# bldc-interface.net
KiCad netlist of a schematic drawn in EAGLE
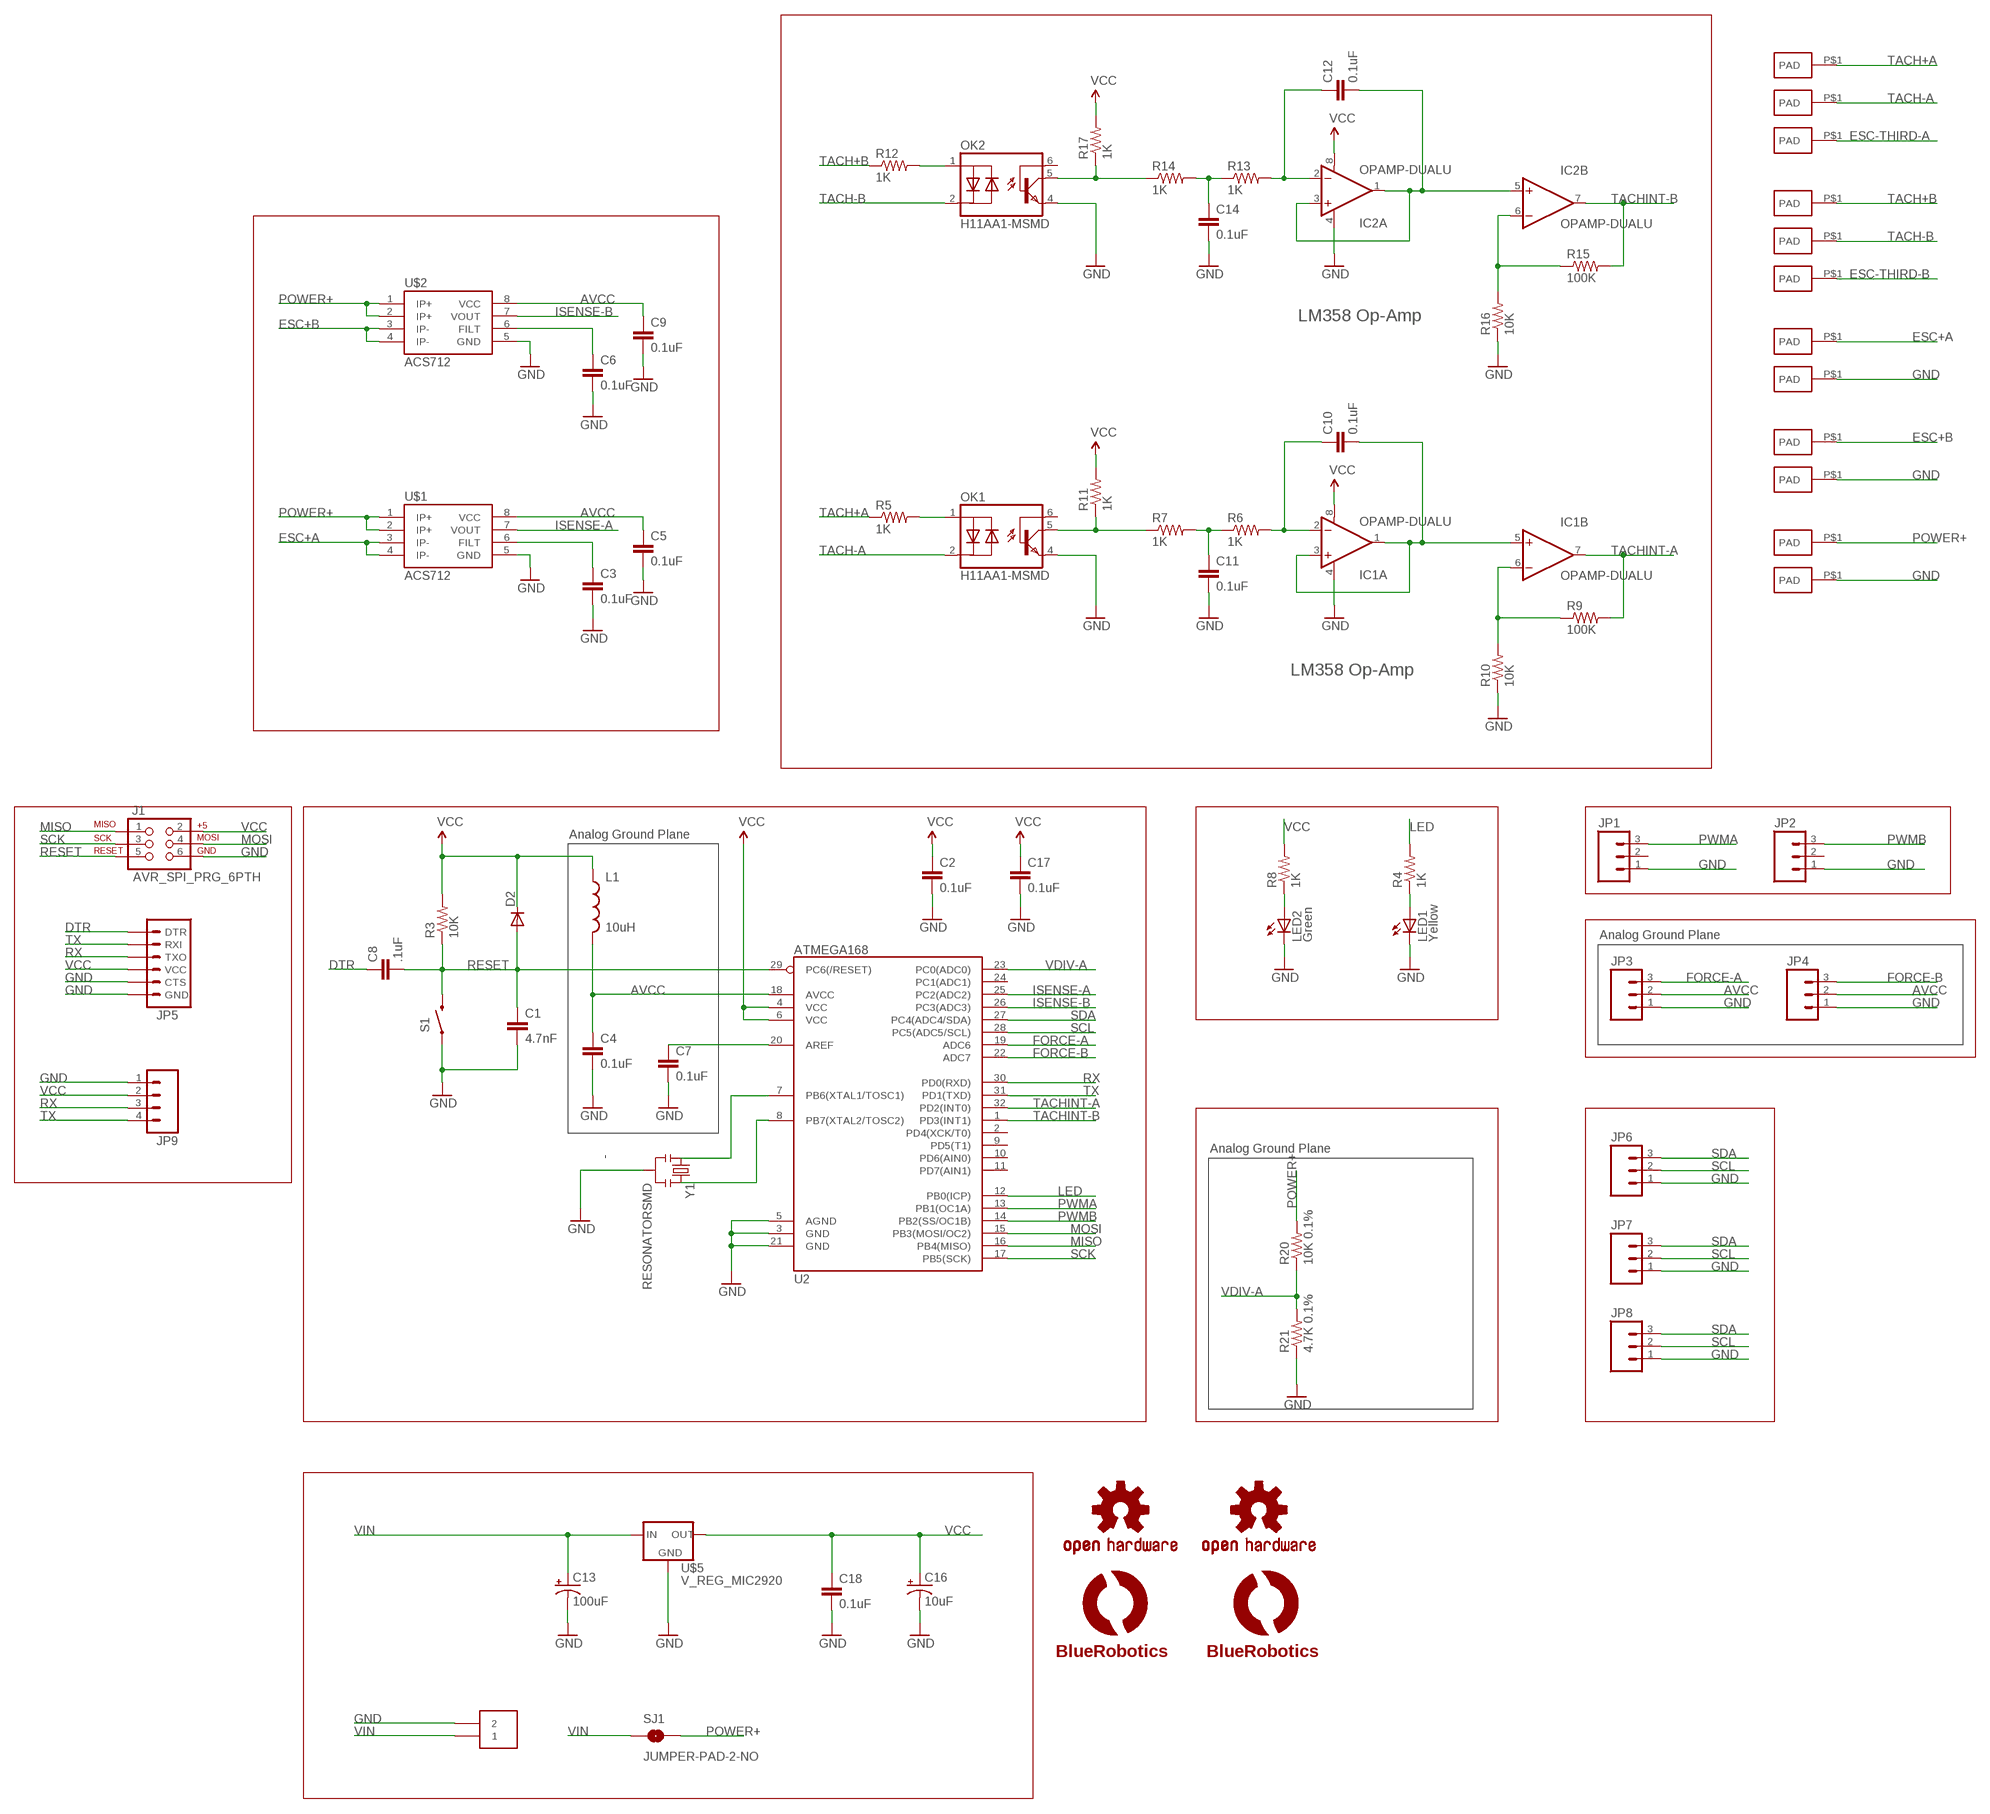
[diagram p0: schematic, sheet 1]

(export (version "E")
  (design (tool "Eeschema 10.0.6"))
  (components
    (comp (ref "C1")
      (value "4.7nF")
      (footprint "eagle-import:0603-CAP")
      (libsource (lib "eagle-import") (part "CAP0603-CAP"))
    )
    (comp (ref "C2")
      (value "0.1uF")
      (footprint "eagle-import:0603-CAP")
      (libsource (lib "eagle-import") (part "SparkFun2_CAP0603-CAP"))
    )
    (comp (ref "C3")
      (value "0.1uF")
      (footprint "eagle-import:0603-CAP")
      (libsource (lib "eagle-import") (part "SparkFun-Capacitors_CAP0603-CAP"))
    )
    (comp (ref "C4")
      (value "0.1uF")
      (footprint "eagle-import:0603-CAP")
      (libsource (lib "eagle-import") (part "CAP0603-CAP"))
    )
    (comp (ref "C5")
      (value "0.1uF")
      (footprint "eagle-import:0603-CAP")
      (libsource (lib "eagle-import") (part "SparkFun-Capacitors_CAP0603-CAP"))
    )
    (comp (ref "C6")
      (value "0.1uF")
      (footprint "eagle-import:0603-CAP")
      (libsource (lib "eagle-import") (part "SparkFun-Capacitors_CAP0603-CAP"))
    )
    (comp (ref "C7")
      (value "0.1uF")
      (footprint "eagle-import:0603-CAP")
      (libsource (lib "eagle-import") (part "CAP0603-CAP"))
    )
    (comp (ref "C8")
      (value ".1uF")
      (footprint "eagle-import:0603-CAP")
      (libsource (lib "eagle-import") (part "CAP0603-CAP"))
    )
    (comp (ref "C9")
      (value "0.1uF")
      (footprint "eagle-import:0603-CAP")
      (libsource (lib "eagle-import") (part "SparkFun-Capacitors_CAP0603-CAP"))
    )
    (comp (ref "C10")
      (value "0.1uF")
      (footprint "eagle-import:0603-CAP")
      (libsource (lib "eagle-import") (part "SparkFun-Capacitors_CAP0603-CAP"))
    )
    (comp (ref "C11")
      (value "0.1uF")
      (footprint "eagle-import:0603-CAP")
      (libsource (lib "eagle-import") (part "SparkFun-Capacitors_CAP0603-CAP"))
    )
    (comp (ref "C12")
      (value "0.1uF")
      (footprint "eagle-import:0603-CAP")
      (libsource (lib "eagle-import") (part "SparkFun-Capacitors_CAP0603-CAP"))
    )
    (comp (ref "C13")
      (value "100uF")
      (footprint "eagle-import:CPOL-RADIAL-100UF-25V")
      (libsource (lib "eagle-import") (part "CAP_POLPTH1"))
    )
    (comp (ref "C14")
      (value "0.1uF")
      (footprint "eagle-import:0603-CAP")
      (libsource (lib "eagle-import") (part "SparkFun-Capacitors_CAP0603-CAP"))
    )
    (comp (ref "C16")
      (value "10uF")
      (footprint "eagle-import:EIA3216")
      (libsource (lib "eagle-import") (part "CAP_POL1206"))
    )
    (comp (ref "C17")
      (value "0.1uF")
      (footprint "eagle-import:0603-CAP")
      (libsource (lib "eagle-import") (part "SparkFun2_CAP0603-CAP"))
    )
    (comp (ref "C18")
      (value "0.1uF")
      (footprint "eagle-import:0603-CAP")
      (libsource (lib "eagle-import") (part "CAP0603-CAP"))
    )
    (comp (ref "D2")
      (value "DIODESOD")
      (footprint "eagle-import:SOD-323")
      (libsource (lib "eagle-import") (part "DIODESOD"))
    )
    (comp (ref "IC1")
      (value "OPAMP-DUALU")
      (footprint "eagle-import:SO08")
      (libsource (lib "eagle-import") (part "OPAMP-DUALU"))
    )
    (comp (ref "IC2")
      (value "OPAMP-DUALU")
      (footprint "eagle-import:SO08")
      (libsource (lib "eagle-import") (part "OPAMP-DUALU"))
    )
    (comp (ref "J1")
      (value "AVR_SPI_PRG_6PTH")
      (footprint "eagle-import:2X3")
      (libsource (lib "eagle-import") (part "AVR_SPI_PRG_6PTH"))
    )
    (comp (ref "JP1")
      (value "M03PTH")
      (footprint "eagle-import:1X03")
      (libsource (lib "eagle-import") (part "M03PTH"))
    )
    (comp (ref "JP2")
      (value "M03PTH")
      (footprint "eagle-import:1X03")
      (libsource (lib "eagle-import") (part "M03PTH"))
    )
    (comp (ref "JP3")
      (value "M03PTH")
      (footprint "eagle-import:1X03")
      (libsource (lib "eagle-import") (part "M03PTH"))
    )
    (comp (ref "JP4")
      (value "M03PTH")
      (footprint "eagle-import:1X03")
      (libsource (lib "eagle-import") (part "M03PTH"))
    )
    (comp (ref "JP5")
      (value "ARDUINO_SERIAL_PROGRAMPTH")
      (footprint "eagle-import:1X06")
      (libsource (lib "eagle-import") (part "ARDUINO_SERIAL_PROGRAMPTH"))
    )
    (comp (ref "JP6")
      (value "M03PTH")
      (footprint "eagle-import:1X03")
      (libsource (lib "eagle-import") (part "M03PTH"))
    )
    (comp (ref "JP7")
      (value "M03PTH")
      (footprint "eagle-import:1X03")
      (libsource (lib "eagle-import") (part "M03PTH"))
    )
    (comp (ref "JP8")
      (value "M03PTH")
      (footprint "eagle-import:1X03")
      (libsource (lib "eagle-import") (part "M03PTH"))
    )
    (comp (ref "JP9")
      (value "M04PTH")
      (footprint "eagle-import:1X04")
      (libsource (lib "eagle-import") (part "M04PTH"))
    )
    (comp (ref "L1")
      (value "10uH")
      (footprint "eagle-import:0603")
      (libsource (lib "eagle-import") (part "INDUCTOR0603"))
    )
    (comp (ref "LED1")
      (value "Yellow")
      (footprint "eagle-import:LED-0603")
      (libsource (lib "eagle-import") (part "LED0603"))
    )
    (comp (ref "LED2")
      (value "Green")
      (footprint "eagle-import:LED-0603")
      (libsource (lib "eagle-import") (part "LED0603"))
    )
    (comp (ref "LOGO1")
      (value "OSHW-LOGOS")
      (footprint "eagle-import:OSHW-LOGO-S")
      (libsource (lib "eagle-import") (part "OSHW-LOGOS"))
    )
    (comp (ref "LOGO2")
      (value "OSHW-LOGOM")
      (footprint "eagle-import:OSHW-LOGO-M")
      (libsource (lib "eagle-import") (part "OSHW-LOGOM"))
    )
    (comp (ref "OK1")
      (value "H11AA1-MSMD")
      (footprint "eagle-import:DIL6-SMD")
      (libsource (lib "eagle-import") (part "H11AA1-MSMD"))
    )
    (comp (ref "OK2")
      (value "H11AA1-MSMD")
      (footprint "eagle-import:DIL6-SMD")
      (libsource (lib "eagle-import") (part "H11AA1-MSMD"))
    )
    (comp (ref "R3")
      (value "10K")
      (footprint "eagle-import:0603-RES")
      (libsource (lib "eagle-import") (part "RESISTOR0603-RES"))
    )
    (comp (ref "R4")
      (value "1K")
      (footprint "eagle-import:0603-RES")
      (libsource (lib "eagle-import") (part "RESISTOR0603-RES"))
    )
    (comp (ref "R5")
      (value "1K")
      (footprint "eagle-import:R2512")
      (libsource (lib "eagle-import") (part "SparkFun-Resistors_RESISTOR2512"))
    )
    (comp (ref "R6")
      (value "1K")
      (footprint "eagle-import:0603-RES")
      (libsource (lib "eagle-import") (part "SparkFun-Resistors_RESISTOR0603-RES"))
    )
    (comp (ref "R7")
      (value "1K")
      (footprint "eagle-import:0603-RES")
      (libsource (lib "eagle-import") (part "SparkFun-Resistors_RESISTOR0603-RES"))
    )
    (comp (ref "R8")
      (value "1K")
      (footprint "eagle-import:0603-RES")
      (libsource (lib "eagle-import") (part "RESISTOR0603-RES"))
    )
    (comp (ref "R9")
      (value "100K")
      (footprint "eagle-import:0603-RES")
      (libsource (lib "eagle-import") (part "SparkFun-Resistors_RESISTOR0603-RES"))
    )
    (comp (ref "R10")
      (value "10K")
      (footprint "eagle-import:0603-RES")
      (libsource (lib "eagle-import") (part "SparkFun-Resistors_RESISTOR0603-RES"))
    )
    (comp (ref "R11")
      (value "1K")
      (footprint "eagle-import:0603-RES")
      (libsource (lib "eagle-import") (part "SparkFun-Resistors_RESISTOR0603-RES"))
    )
    (comp (ref "R12")
      (value "1K")
      (footprint "eagle-import:R2512")
      (libsource (lib "eagle-import") (part "SparkFun-Resistors_RESISTOR2512"))
    )
    (comp (ref "R13")
      (value "1K")
      (footprint "eagle-import:0603-RES")
      (libsource (lib "eagle-import") (part "SparkFun-Resistors_RESISTOR0603-RES"))
    )
    (comp (ref "R14")
      (value "1K")
      (footprint "eagle-import:0603-RES")
      (libsource (lib "eagle-import") (part "SparkFun-Resistors_RESISTOR0603-RES"))
    )
    (comp (ref "R15")
      (value "100K")
      (footprint "eagle-import:0603-RES")
      (libsource (lib "eagle-import") (part "SparkFun-Resistors_RESISTOR0603-RES"))
    )
    (comp (ref "R16")
      (value "10K")
      (footprint "eagle-import:0603-RES")
      (libsource (lib "eagle-import") (part "SparkFun-Resistors_RESISTOR0603-RES"))
    )
    (comp (ref "R17")
      (value "1K")
      (footprint "eagle-import:0603-RES")
      (libsource (lib "eagle-import") (part "SparkFun-Resistors_RESISTOR0603-RES"))
    )
    (comp (ref "R20")
      (value "10K 0.1%")
      (footprint "eagle-import:0603-RES")
      (libsource (lib "eagle-import") (part "RESISTOR0603-RES"))
    )
    (comp (ref "R21")
      (value "4.7K 0.1%")
      (footprint "eagle-import:0603-RES")
      (libsource (lib "eagle-import") (part "RESISTOR0603-RES"))
    )
    (comp (ref "S1")
      (value "reset")
      (footprint "eagle-import:TACTILE_SWITCH_SMD")
      (libsource (lib "eagle-import") (part "SWITCH-MOMENTARY-2SMD"))
    )
    (comp (ref "SJ1")
      (value "JUMPER-PAD-2-NO")
      (footprint "eagle-import:PAD-JUMPER-2-NO_NO_SILK")
      (libsource (lib "eagle-import") (part "JUMPER-PAD-2-NO"))
    )
    (comp (ref "U$1")
      (value "ACS712")
      (footprint "eagle-import:SO08")
      (libsource (lib "eagle-import") (part "ACS712"))
    )
    (comp (ref "U$2")
      (value "ACS712")
      (footprint "eagle-import:SO08")
      (libsource (lib "eagle-import") (part "ACS712"))
    )
    (comp (ref "U$3")
      (value "TERMINAL-25MM-WEID")
      (footprint "eagle-import:LSF-SMT-5MM-2")
      (libsource (lib "eagle-import") (part "TERMINAL-25MM-WEID"))
    )
    (comp (ref "U$4")
      (value "PADLARGE-ONE-SIDE")
      (footprint "eagle-import:PAD-0.2X0.3-ONE-SIDE")
      (libsource (lib "eagle-import") (part "PADLARGE-ONE-SIDE"))
    )
    (comp (ref "U$5")
      (value "V_REG_MIC2920")
      (footprint "eagle-import:SOT223")
      (libsource (lib "eagle-import") (part "V_REG_MIC2920"))
    )
    (comp (ref "U$6")
      (value "PADLARGE-ONE-SIDE")
      (footprint "eagle-import:PAD-0.2X0.3-ONE-SIDE")
      (libsource (lib "eagle-import") (part "PADLARGE-ONE-SIDE"))
    )
    (comp (ref "U$7")
      (value "PADLARGE-ONE-SIDE")
      (footprint "eagle-import:PAD-0.2X0.3-ONE-SIDE")
      (libsource (lib "eagle-import") (part "PADLARGE-ONE-SIDE"))
    )
    (comp (ref "U$8")
      (value "PADLARGE-ONE-SIDE")
      (footprint "eagle-import:PAD-0.2X0.3-ONE-SIDE")
      (libsource (lib "eagle-import") (part "PADLARGE-ONE-SIDE"))
    )
    (comp (ref "U$9")
      (value "PADLARGE-ONE-SIDE")
      (footprint "eagle-import:PAD-0.2X0.3-ONE-SIDE")
      (libsource (lib "eagle-import") (part "PADLARGE-ONE-SIDE"))
    )
    (comp (ref "U$10")
      (value "PADLARGE-ONE-SIDE")
      (footprint "eagle-import:PAD-0.2X0.3-ONE-SIDE")
      (libsource (lib "eagle-import") (part "PADLARGE-ONE-SIDE"))
    )
    (comp (ref "U$11")
      (value "PADLARGE-ONE-SIDE")
      (footprint "eagle-import:PAD-0.2X0.3-ONE-SIDE")
      (libsource (lib "eagle-import") (part "PADLARGE-ONE-SIDE"))
    )
    (comp (ref "U$12")
      (value "PADLARGE-ONE-SIDE")
      (footprint "eagle-import:PAD-0.2X0.3-ONE-SIDE")
      (libsource (lib "eagle-import") (part "PADLARGE-ONE-SIDE"))
    )
    (comp (ref "U$13")
      (value "PADLARGE-ONE-SIDE")
      (footprint "eagle-import:PAD-0.2X0.3-ONE-SIDE")
      (libsource (lib "eagle-import") (part "PADLARGE-ONE-SIDE"))
    )
    (comp (ref "U$14")
      (value "PADLARGE-ONE-SIDE")
      (footprint "eagle-import:PAD-0.2X0.3-ONE-SIDE")
      (libsource (lib "eagle-import") (part "PADLARGE-ONE-SIDE"))
    )
    (comp (ref "U$15")
      (value "PADLARGE-ONE-SIDE")
      (footprint "eagle-import:PAD-0.2X0.3-ONE-SIDE")
      (libsource (lib "eagle-import") (part "PADLARGE-ONE-SIDE"))
    )
    (comp (ref "U$16")
      (value "PADLARGE-ONE-SIDE")
      (footprint "eagle-import:PAD-0.2X0.3-ONE-SIDE")
      (libsource (lib "eagle-import") (part "PADLARGE-ONE-SIDE"))
    )
    (comp (ref "U$17")
      (value "LOGOBR-LOGO-M")
      (footprint "eagle-import:BR-LOGO-MEDIUM")
      (libsource (lib "eagle-import") (part "LOGOBR-LOGO-M"))
    )
    (comp (ref "U$18")
      (value "LOGOBR-LOGO-S")
      (footprint "eagle-import:BR-LOGO-SMALL")
      (libsource (lib "eagle-import") (part "LOGOBR-LOGO-S"))
    )
    (comp (ref "U2")
      (value "ATMEGA168")
      (footprint "eagle-import:TQFP32-08")
      (libsource (lib "eagle-import") (part "ATMEGA168"))
    )
    (comp (ref "Y1")
      (value "RESONATORSMD")
      (footprint "eagle-import:RESONATOR-SMD")
      (libsource (lib "eagle-import") (part "RESONATORSMD"))
    )
  )
  (nets
    (net (code "1") (name "/AVCC") (class "Default")
      (node (ref "C4") (pin "1") (pinfunction "1_1") (pintype "passive"))
      (node (ref "C5") (pin "1") (pinfunction "1_1") (pintype "passive"))
      (node (ref "C9") (pin "1") (pinfunction "1_1") (pintype "passive"))
      (node (ref "JP3") (pin "2") (pinfunction "2_2") (pintype "passive"))
      (node (ref "JP4") (pin "2") (pinfunction "2_2") (pintype "passive"))
      (node (ref "L1") (pin "2") (pinfunction "2_2") (pintype "passive"))
      (node (ref "U$1") (pin "8") (pinfunction "VCC_8") (pintype "bidirectional"))
      (node (ref "U$2") (pin "8") (pinfunction "VCC_8") (pintype "bidirectional"))
      (node (ref "U2") (pin "18") (pinfunction "AVCC_18") (pintype "bidirectional"))
    )
    (net (code "2") (name "/DTR") (class "Default")
      (node (ref "C8") (pin "1") (pinfunction "1_1") (pintype "passive"))
      (node (ref "JP5") (pin "1") (pinfunction "DTR_1") (pintype "passive"))
    )
    (net (code "3") (name "/ESC+A") (class "Default")
      (node (ref "U$1") (pin "3") (pinfunction "IP-_3") (pintype "bidirectional"))
      (node (ref "U$1") (pin "4") (pinfunction "IP-_4") (pintype "bidirectional"))
      (node (ref "U$13") (pin "P$1") (pinfunction "PAD_P$1") (pintype "bidirectional"))
    )
    (net (code "4") (name "/ESC+B") (class "Default")
      (node (ref "U$15") (pin "P$1") (pinfunction "PAD_P$1") (pintype "bidirectional"))
      (node (ref "U$2") (pin "3") (pinfunction "IP-_3") (pintype "bidirectional"))
      (node (ref "U$2") (pin "4") (pinfunction "IP-_4") (pintype "bidirectional"))
    )
    (net (code "5") (name "/ESC-THIRD-A") (class "Default")
      (node (ref "U$9") (pin "P$1") (pinfunction "PAD_P$1") (pintype "bidirectional"))
    )
    (net (code "6") (name "/ESC-THIRD-B") (class "Default")
      (node (ref "U$12") (pin "P$1") (pinfunction "PAD_P$1") (pintype "bidirectional"))
    )
    (net (code "7") (name "/FORCE-A") (class "Default")
      (node (ref "JP3") (pin "3") (pinfunction "3_3") (pintype "passive"))
      (node (ref "U2") (pin "19") (pinfunction "ADC6_19") (pintype "bidirectional"))
    )
    (net (code "8") (name "/FORCE-B") (class "Default")
      (node (ref "JP4") (pin "3") (pinfunction "3_3") (pintype "passive"))
      (node (ref "U2") (pin "22") (pinfunction "ADC7_22") (pintype "bidirectional"))
    )
    (net (code "9") (name "/ISENSE-A") (class "Default")
      (node (ref "U$1") (pin "7") (pinfunction "VOUT_7") (pintype "bidirectional"))
      (node (ref "U2") (pin "25") (pinfunction "PC2(ADC2)_25") (pintype "bidirectional"))
    )
    (net (code "10") (name "/ISENSE-B") (class "Default")
      (node (ref "U$2") (pin "7") (pinfunction "VOUT_7") (pintype "bidirectional"))
      (node (ref "U2") (pin "26") (pinfunction "PC3(ADC3)_26") (pintype "bidirectional"))
    )
    (net (code "11") (name "/LED") (class "Default")
      (node (ref "R4") (pin "2") (pinfunction "2_2") (pintype "passive"))
      (node (ref "U2") (pin "12") (pinfunction "PB0(ICP)_12") (pintype "bidirectional"))
    )
    (net (code "12") (name "/MISO") (class "Default")
      (node (ref "J1") (pin "1") (pinfunction "1_1") (pintype "passive"))
      (node (ref "U2") (pin "16") (pinfunction "PB4(MISO)_16") (pintype "bidirectional"))
    )
    (net (code "13") (name "/MOSI") (class "Default")
      (node (ref "J1") (pin "4") (pinfunction "4_4") (pintype "passive"))
      (node (ref "U2") (pin "15") (pinfunction "PB3(MOSI/OC2)_15") (pintype "bidirectional"))
    )
    (net (code "14") (name "/POWER+") (class "Default")
      (node (ref "R20") (pin "2") (pinfunction "2_2") (pintype "passive"))
      (node (ref "SJ1") (pin "2") (pinfunction "2_2") (pintype "passive"))
      (node (ref "U$1") (pin "1") (pinfunction "IP+_1") (pintype "bidirectional"))
      (node (ref "U$1") (pin "2") (pinfunction "IP+_2") (pintype "bidirectional"))
      (node (ref "U$2") (pin "1") (pinfunction "IP+_1") (pintype "bidirectional"))
      (node (ref "U$2") (pin "2") (pinfunction "IP+_2") (pintype "bidirectional"))
      (node (ref "U$7") (pin "P$1") (pinfunction "PAD_P$1") (pintype "bidirectional"))
    )
    (net (code "15") (name "/PWMA") (class "Default")
      (node (ref "JP1") (pin "3") (pinfunction "3_3") (pintype "passive"))
      (node (ref "U2") (pin "13") (pinfunction "PB1(OC1A)_13") (pintype "bidirectional"))
    )
    (net (code "16") (name "/PWMB") (class "Default")
      (node (ref "JP2") (pin "3") (pinfunction "3_3") (pintype "passive"))
      (node (ref "U2") (pin "14") (pinfunction "PB2(SS/OC1B)_14") (pintype "bidirectional"))
    )
    (net (code "17") (name "/RESET") (class "Default")
      (node (ref "C1") (pin "1") (pinfunction "1_1") (pintype "passive"))
      (node (ref "C8") (pin "2") (pinfunction "2_2") (pintype "passive"))
      (node (ref "D2") (pin "2") (pinfunction "A_2") (pintype "passive"))
      (node (ref "J1") (pin "5") (pinfunction "5_5") (pintype "passive"))
      (node (ref "R3") (pin "1") (pinfunction "1_1") (pintype "passive"))
      (node (ref "S1") (pin "3") (pinfunction "2_3") (pintype "passive"))
      (node (ref "U2") (pin "29") (pinfunction "PC6(/RESET)_29") (pintype "bidirectional"))
    )
    (net (code "18") (name "/RX") (class "Default")
      (node (ref "JP5") (pin "3") (pinfunction "TXO_3") (pintype "passive"))
      (node (ref "JP9") (pin "3") (pinfunction "3_3") (pintype "passive"))
      (node (ref "U2") (pin "30") (pinfunction "PD0(RXD)_30") (pintype "bidirectional"))
    )
    (net (code "19") (name "/SCK") (class "Default")
      (node (ref "J1") (pin "3") (pinfunction "3_3") (pintype "passive"))
      (node (ref "U2") (pin "17") (pinfunction "PB5(SCK)_17") (pintype "bidirectional"))
    )
    (net (code "20") (name "/SCL") (class "Default")
      (node (ref "JP6") (pin "2") (pinfunction "2_2") (pintype "passive"))
      (node (ref "JP7") (pin "2") (pinfunction "2_2") (pintype "passive"))
      (node (ref "JP8") (pin "2") (pinfunction "2_2") (pintype "passive"))
      (node (ref "U2") (pin "28") (pinfunction "PC5(ADC5/SCL)_28") (pintype "bidirectional"))
    )
    (net (code "21") (name "/SDA") (class "Default")
      (node (ref "JP6") (pin "3") (pinfunction "3_3") (pintype "passive"))
      (node (ref "JP7") (pin "3") (pinfunction "3_3") (pintype "passive"))
      (node (ref "JP8") (pin "3") (pinfunction "3_3") (pintype "passive"))
      (node (ref "U2") (pin "27") (pinfunction "PC4(ADC4/SDA)_27") (pintype "bidirectional"))
    )
    (net (code "22") (name "/TACH+A") (class "Default")
      (node (ref "R5") (pin "1") (pinfunction "1_1") (pintype "passive"))
      (node (ref "U$6") (pin "P$1") (pinfunction "PAD_P$1") (pintype "bidirectional"))
    )
    (net (code "23") (name "/TACH+B") (class "Default")
      (node (ref "R12") (pin "1") (pinfunction "1_1") (pintype "passive"))
      (node (ref "U$10") (pin "P$1") (pinfunction "PAD_P$1") (pintype "bidirectional"))
    )
    (net (code "24") (name "/TACH-A") (class "Default")
      (node (ref "OK1") (pin "2") (pinfunction "C_2") (pintype "passive"))
      (node (ref "U$4") (pin "P$1") (pinfunction "PAD_P$1") (pintype "bidirectional"))
    )
    (net (code "25") (name "/TACH-B") (class "Default")
      (node (ref "OK2") (pin "2") (pinfunction "C_2") (pintype "passive"))
      (node (ref "U$11") (pin "P$1") (pinfunction "PAD_P$1") (pintype "bidirectional"))
    )
    (net (code "26") (name "/TACHINT-A") (class "Default")
      (node (ref "IC1") (pin "7") (pinfunction "OUT_7") (pintype "output"))
      (node (ref "R9") (pin "2") (pinfunction "2_2") (pintype "passive"))
      (node (ref "U2") (pin "32") (pinfunction "PD2(INT0)_32") (pintype "bidirectional"))
    )
    (net (code "27") (name "/TACHINT-B") (class "Default")
      (node (ref "IC2") (pin "7") (pinfunction "OUT_7") (pintype "output"))
      (node (ref "R15") (pin "2") (pinfunction "2_2") (pintype "passive"))
      (node (ref "U2") (pin "1") (pinfunction "PD3(INT1)_1") (pintype "bidirectional"))
    )
    (net (code "28") (name "/TX") (class "Default")
      (node (ref "JP5") (pin "2") (pinfunction "RXI_2") (pintype "passive"))
      (node (ref "JP9") (pin "4") (pinfunction "4_4") (pintype "passive"))
      (node (ref "U2") (pin "31") (pinfunction "PD1(TXD)_31") (pintype "bidirectional"))
    )
    (net (code "29") (name "/VDIV-A") (class "Default")
      (node (ref "R20") (pin "1") (pinfunction "1_1") (pintype "passive"))
      (node (ref "R21") (pin "2") (pinfunction "2_2") (pintype "passive"))
      (node (ref "U2") (pin "23") (pinfunction "PC0(ADC0)_23") (pintype "bidirectional"))
    )
    (net (code "30") (name "/VIN") (class "Default")
      (node (ref "C13") (pin "1") (pinfunction "+_1") (pintype "passive"))
      (node (ref "SJ1") (pin "1") (pinfunction "1_1") (pintype "passive"))
      (node (ref "U$3") (pin "1") (pinfunction "1_1") (pintype "bidirectional"))
      (node (ref "U$3") (pin "3") (pinfunction "1_3") (pintype "bidirectional"))
      (node (ref "U$5") (pin "1") (pinfunction "IN_1") (pintype "input"))
    )
    (net (code "31") (name "GND") (class "Default")
      (node (ref "C1") (pin "2") (pinfunction "2_2") (pintype "passive"))
      (node (ref "C11") (pin "2") (pinfunction "2_2") (pintype "passive"))
      (node (ref "C13") (pin "2") (pinfunction "-_2") (pintype "passive"))
      (node (ref "C14") (pin "2") (pinfunction "2_2") (pintype "passive"))
      (node (ref "C16") (pin "C") (pinfunction "-_C") (pintype "passive"))
      (node (ref "C17") (pin "2") (pinfunction "2_2") (pintype "passive"))
      (node (ref "C18") (pin "2") (pinfunction "2_2") (pintype "passive"))
      (node (ref "C2") (pin "2") (pinfunction "2_2") (pintype "passive"))
      (node (ref "C3") (pin "2") (pinfunction "2_2") (pintype "passive"))
      (node (ref "C4") (pin "2") (pinfunction "2_2") (pintype "passive"))
      (node (ref "C5") (pin "2") (pinfunction "2_2") (pintype "passive"))
      (node (ref "C6") (pin "2") (pinfunction "2_2") (pintype "passive"))
      (node (ref "C7") (pin "2") (pinfunction "2_2") (pintype "passive"))
      (node (ref "C9") (pin "2") (pinfunction "2_2") (pintype "passive"))
      (node (ref "IC1") (pin "4") (pinfunction "V-_4") (pintype "power_in"))
      (node (ref "IC2") (pin "4") (pinfunction "V-_4") (pintype "power_in"))
      (node (ref "J1") (pin "6") (pinfunction "6_6") (pintype "passive"))
      (node (ref "JP1") (pin "1") (pinfunction "1_1") (pintype "passive"))
      (node (ref "JP2") (pin "1") (pinfunction "1_1") (pintype "passive"))
      (node (ref "JP3") (pin "1") (pinfunction "1_1") (pintype "passive"))
      (node (ref "JP4") (pin "1") (pinfunction "1_1") (pintype "passive"))
      (node (ref "JP5") (pin "5") (pinfunction "CTS_5") (pintype "passive"))
      (node (ref "JP5") (pin "6") (pinfunction "GND_6") (pintype "passive"))
      (node (ref "JP6") (pin "1") (pinfunction "1_1") (pintype "passive"))
      (node (ref "JP7") (pin "1") (pinfunction "1_1") (pintype "passive"))
      (node (ref "JP8") (pin "1") (pinfunction "1_1") (pintype "passive"))
      (node (ref "JP9") (pin "1") (pinfunction "1_1") (pintype "passive"))
      (node (ref "LED1") (pin "C") (pinfunction "C_C") (pintype "passive"))
      (node (ref "LED2") (pin "C") (pinfunction "C_C") (pintype "passive"))
      (node (ref "OK1") (pin "4") (pinfunction "EMI_4") (pintype "passive"))
      (node (ref "OK2") (pin "4") (pinfunction "EMI_4") (pintype "passive"))
      (node (ref "R10") (pin "1") (pinfunction "1_1") (pintype "passive"))
      (node (ref "R16") (pin "1") (pinfunction "1_1") (pintype "passive"))
      (node (ref "R21") (pin "1") (pinfunction "1_1") (pintype "passive"))
      (node (ref "S1") (pin "1") (pinfunction "1_1") (pintype "passive"))
      (node (ref "U$1") (pin "5") (pinfunction "GND_5") (pintype "bidirectional"))
      (node (ref "U$14") (pin "P$1") (pinfunction "PAD_P$1") (pintype "bidirectional"))
      (node (ref "U$16") (pin "P$1") (pinfunction "PAD_P$1") (pintype "bidirectional"))
      (node (ref "U$2") (pin "5") (pinfunction "GND_5") (pintype "bidirectional"))
      (node (ref "U$3") (pin "2") (pinfunction "2_2") (pintype "bidirectional"))
      (node (ref "U$3") (pin "4") (pinfunction "2_4") (pintype "bidirectional"))
      (node (ref "U$5") (pin "2") (pinfunction "GND_2") (pintype "input"))
      (node (ref "U$8") (pin "P$1") (pinfunction "PAD_P$1") (pintype "bidirectional"))
      (node (ref "U2") (pin "21") (pinfunction "GND_21") (pintype "bidirectional"))
      (node (ref "U2") (pin "3") (pinfunction "GND_3") (pintype "bidirectional"))
      (node (ref "U2") (pin "5") (pinfunction "AGND_5") (pintype "bidirectional"))
      (node (ref "Y1") (pin "2") (pinfunction "2_2") (pintype "passive"))
    )
    (net (code "32") (name "Net-(C11-Pad1)") (class "Default")
      (node (ref "C11") (pin "1") (pinfunction "1_1") (pintype "passive"))
      (node (ref "R6") (pin "1") (pinfunction "1_1") (pintype "passive"))
      (node (ref "R7") (pin "2") (pinfunction "2_2") (pintype "passive"))
    )
    (net (code "33") (name "Net-(C14-Pad1)") (class "Default")
      (node (ref "C14") (pin "1") (pinfunction "1_1") (pintype "passive"))
      (node (ref "R13") (pin "1") (pinfunction "1_1") (pintype "passive"))
      (node (ref "R14") (pin "2") (pinfunction "2_2") (pintype "passive"))
    )
    (net (code "34") (name "Net-(IC1A-+IN)") (class "Default")
      (node (ref "C10") (pin "2") (pinfunction "2_2") (pintype "passive"))
      (node (ref "IC1") (pin "1") (pinfunction "OUT_1") (pintype "output"))
      (node (ref "IC1") (pin "3") (pinfunction "+IN_3") (pintype "input"))
      (node (ref "IC1") (pin "5") (pinfunction "+IN_5") (pintype "input"))
    )
    (net (code "35") (name "Net-(IC1A--IN)") (class "Default")
      (node (ref "C10") (pin "1") (pinfunction "1_1") (pintype "passive"))
      (node (ref "IC1") (pin "2") (pinfunction "-IN_2") (pintype "input"))
      (node (ref "R6") (pin "2") (pinfunction "2_2") (pintype "passive"))
    )
    (net (code "36") (name "Net-(IC1B--IN)") (class "Default")
      (node (ref "IC1") (pin "6") (pinfunction "-IN_6") (pintype "input"))
      (node (ref "R10") (pin "2") (pinfunction "2_2") (pintype "passive"))
      (node (ref "R9") (pin "1") (pinfunction "1_1") (pintype "passive"))
    )
    (net (code "37") (name "Net-(IC2A-+IN)") (class "Default")
      (node (ref "C12") (pin "2") (pinfunction "2_2") (pintype "passive"))
      (node (ref "IC2") (pin "1") (pinfunction "OUT_1") (pintype "output"))
      (node (ref "IC2") (pin "3") (pinfunction "+IN_3") (pintype "input"))
      (node (ref "IC2") (pin "5") (pinfunction "+IN_5") (pintype "input"))
    )
    (net (code "38") (name "Net-(IC2A--IN)") (class "Default")
      (node (ref "C12") (pin "1") (pinfunction "1_1") (pintype "passive"))
      (node (ref "IC2") (pin "2") (pinfunction "-IN_2") (pintype "input"))
      (node (ref "R13") (pin "2") (pinfunction "2_2") (pintype "passive"))
    )
    (net (code "39") (name "Net-(IC2B--IN)") (class "Default")
      (node (ref "IC2") (pin "6") (pinfunction "-IN_6") (pintype "input"))
      (node (ref "R15") (pin "1") (pinfunction "1_1") (pintype "passive"))
      (node (ref "R16") (pin "2") (pinfunction "2_2") (pintype "passive"))
    )
    (net (code "40") (name "Net-(LED1-PadA)") (class "Default")
      (node (ref "LED1") (pin "A") (pinfunction "A_A") (pintype "passive"))
      (node (ref "R4") (pin "1") (pinfunction "1_1") (pintype "passive"))
    )
    (net (code "41") (name "Net-(LED2-PadA)") (class "Default")
      (node (ref "LED2") (pin "A") (pinfunction "A_A") (pintype "passive"))
      (node (ref "R8") (pin "1") (pinfunction "1_1") (pintype "passive"))
    )
    (net (code "42") (name "Net-(OK1-A)") (class "Default")
      (node (ref "OK1") (pin "1") (pinfunction "A_1") (pintype "passive"))
      (node (ref "R5") (pin "2") (pinfunction "2_2") (pintype "passive"))
    )
    (net (code "43") (name "Net-(OK1-COL)") (class "Default")
      (node (ref "OK1") (pin "5") (pinfunction "COL_5") (pintype "passive"))
      (node (ref "R11") (pin "1") (pinfunction "1_1") (pintype "passive"))
      (node (ref "R7") (pin "1") (pinfunction "1_1") (pintype "passive"))
    )
    (net (code "44") (name "Net-(OK2-A)") (class "Default")
      (node (ref "OK2") (pin "1") (pinfunction "A_1") (pintype "passive"))
      (node (ref "R12") (pin "2") (pinfunction "2_2") (pintype "passive"))
    )
    (net (code "45") (name "Net-(OK2-COL)") (class "Default")
      (node (ref "OK2") (pin "5") (pinfunction "COL_5") (pintype "passive"))
      (node (ref "R14") (pin "1") (pinfunction "1_1") (pintype "passive"))
      (node (ref "R17") (pin "1") (pinfunction "1_1") (pintype "passive"))
    )
    (net (code "46") (name "Net-(U$1-FILT)") (class "Default")
      (node (ref "C3") (pin "1") (pinfunction "1_1") (pintype "passive"))
      (node (ref "U$1") (pin "6") (pinfunction "FILT_6") (pintype "bidirectional"))
    )
    (net (code "47") (name "Net-(U$2-FILT)") (class "Default")
      (node (ref "C6") (pin "1") (pinfunction "1_1") (pintype "passive"))
      (node (ref "U$2") (pin "6") (pinfunction "FILT_6") (pintype "bidirectional"))
    )
    (net (code "48") (name "Net-(U2-AREF)") (class "Default")
      (node (ref "C7") (pin "1") (pinfunction "1_1") (pintype "passive"))
      (node (ref "U2") (pin "20") (pinfunction "AREF_20") (pintype "bidirectional"))
    )
    (net (code "49") (name "Net-(U2-PB6(XTAL1{slash}TOSC1))") (class "Default")
      (node (ref "U2") (pin "7") (pinfunction "PB6(XTAL1/TOSC1)_7") (pintype "bidirectional"))
      (node (ref "Y1") (pin "1") (pinfunction "1_1") (pintype "passive"))
    )
    (net (code "50") (name "Net-(U2-PB7(XTAL2{slash}TOSC2))") (class "Default")
      (node (ref "U2") (pin "8") (pinfunction "PB7(XTAL2/TOSC2)_8") (pintype "bidirectional"))
      (node (ref "Y1") (pin "3") (pinfunction "3_3") (pintype "passive"))
    )
    (net (code "51") (name "VCC") (class "Default")
      (node (ref "C16") (pin "A") (pinfunction "+_A") (pintype "passive"))
      (node (ref "C17") (pin "1") (pinfunction "1_1") (pintype "passive"))
      (node (ref "C18") (pin "1") (pinfunction "1_1") (pintype "passive"))
      (node (ref "C2") (pin "1") (pinfunction "1_1") (pintype "passive"))
      (node (ref "D2") (pin "1") (pinfunction "C_1") (pintype "passive"))
      (node (ref "IC1") (pin "8") (pinfunction "V+_8") (pintype "power_in"))
      (node (ref "IC2") (pin "8") (pinfunction "V+_8") (pintype "power_in"))
      (node (ref "J1") (pin "2") (pinfunction "2_2") (pintype "passive"))
      (node (ref "JP5") (pin "4") (pinfunction "VCC_4") (pintype "passive"))
      (node (ref "JP9") (pin "2") (pinfunction "2_2") (pintype "passive"))
      (node (ref "L1") (pin "1") (pinfunction "1_1") (pintype "passive"))
      (node (ref "R11") (pin "2") (pinfunction "2_2") (pintype "passive"))
      (node (ref "R17") (pin "2") (pinfunction "2_2") (pintype "passive"))
      (node (ref "R3") (pin "2") (pinfunction "2_2") (pintype "passive"))
      (node (ref "R8") (pin "2") (pinfunction "2_2") (pintype "passive"))
      (node (ref "U$5") (pin "3") (pinfunction "OUT_3") (pintype "output"))
      (node (ref "U2") (pin "4") (pinfunction "VCC_4") (pintype "bidirectional"))
      (node (ref "U2") (pin "6") (pinfunction "VCC_6") (pintype "bidirectional"))
    )
    (net (code "52") (name "unconnected-(JP1-Pad2)") (class "Default")
      (node (ref "JP1") (pin "2") (pinfunction "2_2") (pintype "passive"))
    )
    (net (code "53") (name "unconnected-(JP2-Pad2)") (class "Default")
      (node (ref "JP2") (pin "2") (pinfunction "2_2") (pintype "passive"))
    )
    (net (code "54") (name "unconnected-(OK1-BAS-Pad6)") (class "Default")
      (node (ref "OK1") (pin "6") (pinfunction "BAS_6") (pintype "passive"))
    )
    (net (code "55") (name "unconnected-(OK2-BAS-Pad6)") (class "Default")
      (node (ref "OK2") (pin "6") (pinfunction "BAS_6") (pintype "passive"))
    )
    (net (code "56") (name "unconnected-(U2-PC1(ADC1)-Pad24)") (class "Default")
      (node (ref "U2") (pin "24") (pinfunction "PC1(ADC1)_24") (pintype "bidirectional"))
    )
    (net (code "57") (name "unconnected-(U2-PD4(XCK{slash}T0)-Pad2)") (class "Default")
      (node (ref "U2") (pin "2") (pinfunction "PD4(XCK/T0)_2") (pintype "bidirectional"))
    )
    (net (code "58") (name "unconnected-(U2-PD5(T1)-Pad9)") (class "Default")
      (node (ref "U2") (pin "9") (pinfunction "PD5(T1)_9") (pintype "bidirectional"))
    )
    (net (code "59") (name "unconnected-(U2-PD6(AIN0)-Pad10)") (class "Default")
      (node (ref "U2") (pin "10") (pinfunction "PD6(AIN0)_10") (pintype "bidirectional"))
    )
    (net (code "60") (name "unconnected-(U2-PD7(AIN1)-Pad11)") (class "Default")
      (node (ref "U2") (pin "11") (pinfunction "PD7(AIN1)_11") (pintype "bidirectional"))
    )
  )
)
